# Par_Conditioning.net
KiCad netlist of a schematic drawn in Altium Designer
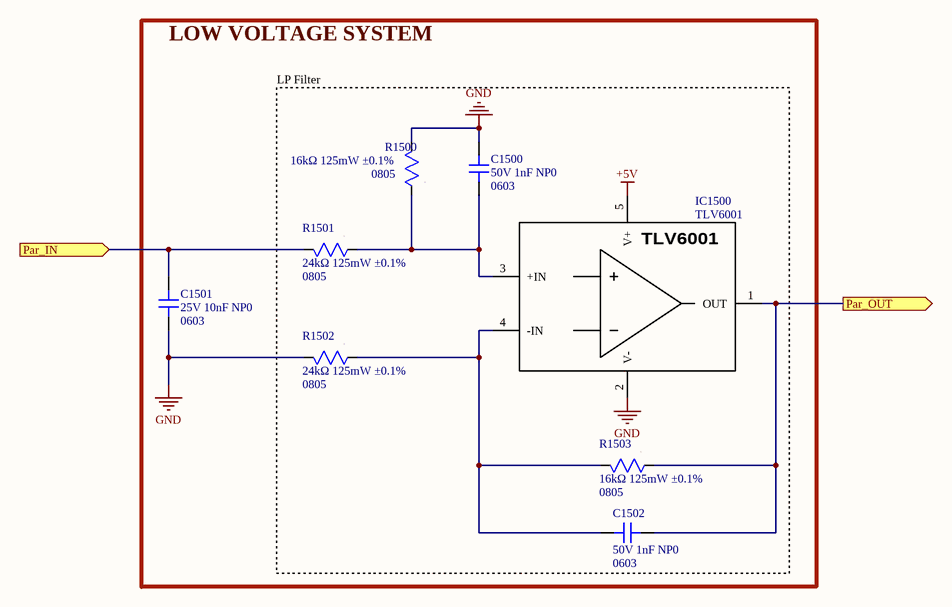
[diagram p0: Par_Conditioning.SchDoc]

(export (version "E")
  (design (tool "Eeschema 10.0.6"))
  (components
    (comp (ref "C1500")
      (value "50V 1nF NP0")
      (footprint "CAP SMD 0603")
      (description "Condensadores de cerámica multicapa (MLCC- SMD/SMT) WCAP-CSGP 1000pF 0603 5% 50V MLCC")
      (fields
        (field (name "PACKAGE") "0603")
        (field (name "MPN") "885012006063")
        (field (name "MANUFACTURER") "Wurth Elektronik")
      )
      (libsource (lib "eUSR_Database") (part "CAP non polarized"))
    )
    (comp (ref "C1501")
      (value "25V 10nF NP0")
      (footprint "CAP SMD 0603")
      (description "Condensadores de cerámica multicapa (MLCC- SMD/SMT) 0.01 uF 25 VDC 1% 0603 C0G (NP0) AEC-Q200")
      (fields
        (field (name "PACKAGE") "0603")
        (field (name "MPN") "GRT1885C1E103FA02D")
        (field (name "MANUFACTURER") "muRata")
      )
      (libsource (lib "eUSR_Database") (part "CAP non polarized"))
    )
    (comp (ref "C1502")
      (value "50V 1nF NP0")
      (footprint "CAP SMD 0603")
      (description "Condensadores de cerámica multicapa (MLCC- SMD/SMT) WCAP-CSGP 1000pF 0603 5% 50V MLCC")
      (fields
        (field (name "PACKAGE") "0603")
        (field (name "MPN") "885012006063")
        (field (name "MANUFACTURER") "Wurth Elektronik")
      )
      (libsource (lib "eUSR_Database") (part "CAP non polarized"))
    )
    (comp (ref "IC1500")
      (value "TLV6001")
      (footprint "SOT-23-5")
      (fields (field (name "MPN") "TLV6001UIDBVR") (field (name "MANUFACTURER") "Texas Instruments"))
      (libsource (lib "eUSR_Database") (part "TLV6001"))
    )
    (comp (ref "R1500")
      (value "16kΩ 125mW ±0.1%")
      (footprint "RES SMD 0805")
      (description "Resistores de película fina - SMD 0805 16Kohm 0.1% 10ppm AEC-Q200")
      (fields
        (field (name "PACKAGE") "0805")
        (field (name "MPN") "ERA-6ARB163V")
        (field (name "MANUFACTURER") "Panasonic")
      )
      (libsource (lib "eUSR_Database") (part "RES"))
    )
    (comp (ref "R1501")
      (value "24kΩ 125mW ±0.1%")
      (footprint "RES SMD 0805")
      (description "Resistores de película fina - SMD 0805 24Kohm 0.1% 15ppm AEC-Q200")
      (fields
        (field (name "PACKAGE") "0805")
        (field (name "MPN") "ERA-6APB243V")
        (field (name "MANUFACTURER") "Panasonic")
      )
      (libsource (lib "eUSR_Database") (part "RES"))
    )
    (comp (ref "R1502")
      (value "24kΩ 125mW ±0.1%")
      (footprint "RES SMD 0805")
      (description "Resistores de película fina - SMD 0805 24Kohm 0.1% 15ppm AEC-Q200")
      (fields
        (field (name "PACKAGE") "0805")
        (field (name "MPN") "ERA-6APB243V")
        (field (name "MANUFACTURER") "Panasonic")
      )
      (libsource (lib "eUSR_Database") (part "RES"))
    )
    (comp (ref "R1503")
      (value "16kΩ 125mW ±0.1%")
      (footprint "RES SMD 0805")
      (description "Resistores de película fina - SMD 0805 16Kohm 0.1% 10ppm AEC-Q200")
      (fields
        (field (name "PACKAGE") "0805")
        (field (name "MPN") "ERA-6ARB163V")
        (field (name "MANUFACTURER") "Panasonic")
      )
      (libsource (lib "eUSR_Database") (part "RES"))
    )
  )
  (nets
    (net (code "1") (name "+5V") (class "Default")
      (node (ref "IC1500") (pin "5") (pinfunction "V+_5") (pintype "passive"))
    )
    (net (code "2") (name "/Par_IN") (class "Default")
      (node (ref "C1501") (pin "1") (pinfunction "1_1") (pintype "passive"))
      (node (ref "R1501") (pin "2") (pinfunction "2_2") (pintype "passive"))
    )
    (net (code "3") (name "/Par_OUT") (class "Default")
      (node (ref "C1502") (pin "2") (pinfunction "2_2") (pintype "passive"))
      (node (ref "IC1500") (pin "1") (pinfunction "OUT_1") (pintype "passive"))
      (node (ref "R1503") (pin "1") (pinfunction "1_1") (pintype "passive"))
    )
    (net (code "4") (name "GND") (class "Default")
      (node (ref "C1500") (pin "1") (pinfunction "1_1") (pintype "passive"))
      (node (ref "C1501") (pin "2") (pinfunction "2_2") (pintype "passive"))
      (node (ref "IC1500") (pin "2") (pinfunction "V-_2") (pintype "passive"))
      (node (ref "R1500") (pin "2") (pinfunction "2_2") (pintype "passive"))
      (node (ref "R1502") (pin "2") (pinfunction "2_2") (pintype "passive"))
    )
    (net (code "5") (name "Net-(IC1500-+IN)") (class "Default")
      (node (ref "C1500") (pin "2") (pinfunction "2_2") (pintype "passive"))
      (node (ref "IC1500") (pin "3") (pinfunction "+IN_3") (pintype "passive"))
      (node (ref "R1500") (pin "1") (pinfunction "1_1") (pintype "passive"))
      (node (ref "R1501") (pin "1") (pinfunction "1_1") (pintype "passive"))
    )
    (net (code "6") (name "Net-(IC1500--IN)") (class "Default")
      (node (ref "C1502") (pin "1") (pinfunction "1_1") (pintype "passive"))
      (node (ref "IC1500") (pin "4") (pinfunction "-IN_4") (pintype "passive"))
      (node (ref "R1502") (pin "1") (pinfunction "1_1") (pintype "passive"))
      (node (ref "R1503") (pin "2") (pinfunction "2_2") (pintype "passive"))
    )
  )
)
